# rare.net
KiCad netlist of a schematic drawn in EAGLE
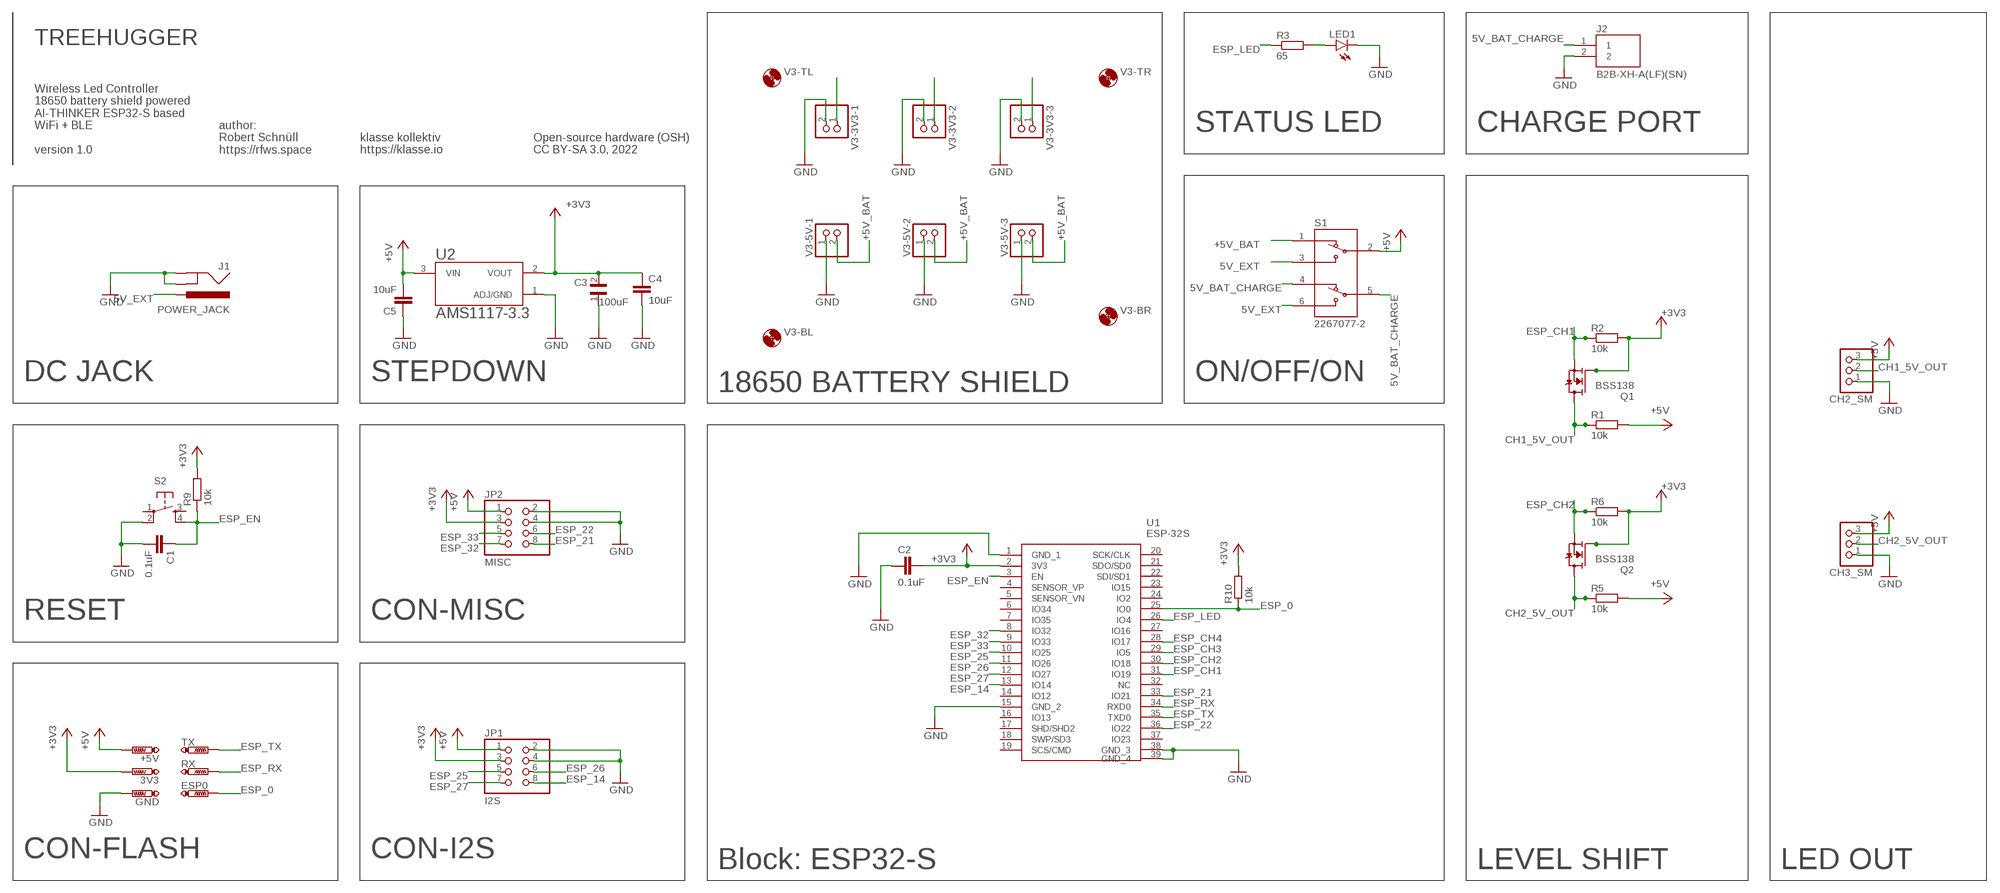
[diagram p0: schematic, sheet 1]

(export (version "E")
  (design (tool "Eeschema 10.0.6"))
  (components
    (comp (ref "+5V")
      (value "PTR1TP15R")
      (footprint "eagle-import:TP15R")
      (libsource (lib "eagle-import") (part "PTR1TP15R"))
    )
    (comp (ref "3V3")
      (value "PTR1TP15R")
      (footprint "eagle-import:TP15R")
      (libsource (lib "eagle-import") (part "PTR1TP15R"))
    )
    (comp (ref "C1")
      (value "0.1uF")
      (footprint "eagle-import:C0805")
      (libsource (lib "eagle-import") (part "C-EUC0805"))
    )
    (comp (ref "C2")
      (value "0.1uF")
      (footprint "eagle-import:C0805")
      (libsource (lib "eagle-import") (part "C-EUC0805"))
    )
    (comp (ref "C3")
      (value "100uF")
      (footprint "eagle-import:CAPPC3528X210N")
      (fields (field (name "MF") "AVX") (field (name "MP") "TAJB107K006RNJ"))
      (libsource (lib "eagle-import") (part "TAJB107K006RNJ"))
    )
    (comp (ref "C4")
      (value "10uF")
      (footprint "eagle-import:C0805")
      (libsource (lib "eagle-import") (part "C-EUC0805"))
    )
    (comp (ref "C5")
      (value "10uF")
      (footprint "eagle-import:C0805")
      (libsource (lib "eagle-import") (part "C-EUC0805"))
    )
    (comp (ref "CH2_SM")
      (value "PINHD-1X3/90")
      (footprint "eagle-import:1X03_90")
      (libsource (lib "eagle-import") (part "PINHD-1X3/90"))
    )
    (comp (ref "CH3_SM")
      (value "PINHD-1X3/90")
      (footprint "eagle-import:1X03_90")
      (libsource (lib "eagle-import") (part "PINHD-1X3/90"))
    )
    (comp (ref "ESP0")
      (value "PTR1TP15R")
      (footprint "eagle-import:TP15R")
      (libsource (lib "eagle-import") (part "PTR1TP15R"))
    )
    (comp (ref "GND")
      (value "PTR1TP15R")
      (footprint "eagle-import:TP15R")
      (libsource (lib "eagle-import") (part "PTR1TP15R"))
    )
    (comp (ref "J1")
      (value "POWER_JACK")
      (footprint "eagle-import:POWER_JACK_PTH")
      (libsource (lib "eagle-import") (part "POWER_JACK"))
    )
    (comp (ref "J2")
      (value "B2B-XH-A(LF)(SN)")
      (footprint "eagle-import:JST_B2B-XH-A(LF)(SN)")
      (fields (field (name "MF") "JST Sales America Inc."))
      (libsource (lib "eagle-import") (part "B2B-XH-A(LF)(SN)"))
    )
    (comp (ref "JP1")
      (value "I2S")
      (footprint "eagle-import:2X04")
      (libsource (lib "eagle-import") (part "PINHD-2X4"))
    )
    (comp (ref "JP2")
      (value "MISC")
      (footprint "eagle-import:2X04")
      (libsource (lib "eagle-import") (part "PINHD-2X4"))
    )
    (comp (ref "LED1")
      (value "LEDCHIP-LED0805")
      (footprint "eagle-import:CHIP-LED0805")
      (libsource (lib "eagle-import") (part "LEDCHIP-LED0805"))
    )
    (comp (ref "Q1")
      (value "BSS138")
      (footprint "eagle-import:SOT23")
      (fields (field (name "MF") "Fairchild"))
      (libsource (lib "eagle-import") (part "BSS138"))
    )
    (comp (ref "Q2")
      (value "BSS138")
      (footprint "eagle-import:SOT23")
      (fields (field (name "MF") "Fairchild"))
      (libsource (lib "eagle-import") (part "BSS138"))
    )
    (comp (ref "R1")
      (value "10k")
      (footprint "eagle-import:R0805")
      (libsource (lib "eagle-import") (part "resistor_348_R-EU_R0805"))
    )
    (comp (ref "R2")
      (value "10k")
      (footprint "eagle-import:R0805")
      (libsource (lib "eagle-import") (part "resistor_348_R-EU_R0805"))
    )
    (comp (ref "R3")
      (value "65")
      (footprint "eagle-import:R0805")
      (libsource (lib "eagle-import") (part "R-EU_R0805"))
    )
    (comp (ref "R5")
      (value "10k")
      (footprint "eagle-import:R0805")
      (libsource (lib "eagle-import") (part "resistor_348_R-EU_R0805"))
    )
    (comp (ref "R6")
      (value "10k")
      (footprint "eagle-import:R0805")
      (libsource (lib "eagle-import") (part "resistor_348_R-EU_R0805"))
    )
    (comp (ref "R9")
      (value "10k")
      (footprint "eagle-import:R0805")
      (libsource (lib "eagle-import") (part "R-EU_R0805"))
    )
    (comp (ref "R10")
      (value "10k")
      (footprint "eagle-import:R0805")
      (libsource (lib "eagle-import") (part "R-EU_R0805"))
    )
    (comp (ref "RX")
      (value "PTR1TP15R")
      (footprint "eagle-import:TP15R")
      (libsource (lib "eagle-import") (part "PTR1TP15R"))
    )
    (comp (ref "S1")
      (value "2267077-2")
      (footprint "eagle-import:TE_2267077-2")
      (fields (field (name "MF") "TE Connectivity"))
      (libsource (lib "eagle-import") (part "2267077-2"))
    )
    (comp (ref "S2")
      (value "TAC_SWITCHSMD")
      (footprint "eagle-import:TACTILE_SWITCH_SMD")
      (libsource (lib "eagle-import") (part "TAC_SWITCHSMD"))
    )
    (comp (ref "TX")
      (value "PTR1TP15R")
      (footprint "eagle-import:TP15R")
      (libsource (lib "eagle-import") (part "PTR1TP15R"))
    )
    (comp (ref "U1")
      (value "ESP-32S")
      (footprint "eagle-import:ESP-32S")
      (fields (field (name "MANUFACTURER_PART_NUMBER") "ESP-32s"))
      (libsource (lib "eagle-import") (part "ESP-32S"))
    )
    (comp (ref "U2")
      (value "AMS1117-3.3")
      (footprint "eagle-import:SOT229P700X180-4N")
      (fields (field (name "MF") "Advanced Monolithic Systems"))
      (libsource (lib "eagle-import") (part "AMS1117-3.3"))
    )
    (comp (ref "V3-3V3-1")
      (value "PINHD-1X2")
      (footprint "eagle-import:1X02")
      (libsource (lib "eagle-import") (part "PINHD-1X2"))
    )
    (comp (ref "V3-3V3-2")
      (value "PINHD-1X2")
      (footprint "eagle-import:1X02")
      (libsource (lib "eagle-import") (part "PINHD-1X2"))
    )
    (comp (ref "V3-3V3-3")
      (value "PINHD-1X2")
      (footprint "eagle-import:1X02")
      (libsource (lib "eagle-import") (part "PINHD-1X2"))
    )
    (comp (ref "V3-5V-1")
      (value "PINHD-1X2")
      (footprint "eagle-import:1X02")
      (libsource (lib "eagle-import") (part "PINHD-1X2"))
    )
    (comp (ref "V3-5V-2")
      (value "PINHD-1X2")
      (footprint "eagle-import:1X02")
      (libsource (lib "eagle-import") (part "PINHD-1X2"))
    )
    (comp (ref "V3-5V-3")
      (value "PINHD-1X2")
      (footprint "eagle-import:1X02")
      (libsource (lib "eagle-import") (part "PINHD-1X2"))
    )
    (comp (ref "V3-BL")
      (value "MOUNT-HOLE3.2")
      (footprint "eagle-import:3,2")
      (libsource (lib "eagle-import") (part "MOUNT-HOLE3.2"))
    )
    (comp (ref "V3-BR")
      (value "MOUNT-HOLE3.2")
      (footprint "eagle-import:3,2")
      (libsource (lib "eagle-import") (part "MOUNT-HOLE3.2"))
    )
    (comp (ref "V3-TL")
      (value "MOUNT-HOLE3.2")
      (footprint "eagle-import:3,2")
      (libsource (lib "eagle-import") (part "MOUNT-HOLE3.2"))
    )
    (comp (ref "V3-TR")
      (value "MOUNT-HOLE3.2")
      (footprint "eagle-import:3,2")
      (libsource (lib "eagle-import") (part "MOUNT-HOLE3.2"))
    )
  )
  (nets
    (net (code "1") (name "+3V3") (class "Default")
      (node (ref "3V3") (pin "TP") (pinfunction "TP_TP") (pintype "input"))
      (node (ref "C2") (pin "2") (pinfunction "2_2") (pintype "passive"))
      (node (ref "C3") (pin "2") (pinfunction "2_2") (pintype "passive"))
      (node (ref "C4") (pin "1") (pinfunction "1_1") (pintype "passive"))
      (node (ref "JP1") (pin "3") (pinfunction "3_3") (pintype "passive"))
      (node (ref "JP2") (pin "3") (pinfunction "3_3") (pintype "passive"))
      (node (ref "Q1") (pin "1") (pinfunction "G_1") (pintype "passive"))
      (node (ref "Q2") (pin "1") (pinfunction "G_1") (pintype "passive"))
      (node (ref "R10") (pin "2") (pinfunction "2_2") (pintype "passive"))
      (node (ref "R2") (pin "2") (pinfunction "2_2") (pintype "passive"))
      (node (ref "R6") (pin "2") (pinfunction "2_2") (pintype "passive"))
      (node (ref "R9") (pin "2") (pinfunction "2_2") (pintype "passive"))
      (node (ref "U1") (pin "2") (pinfunction "3V3_2") (pintype "bidirectional"))
      (node (ref "U2") (pin "2") (pinfunction "VOUT_2") (pintype "output"))
    )
    (net (code "2") (name "+5V") (class "Default")
      (node (ref "+5V") (pin "TP") (pinfunction "TP_TP") (pintype "input"))
      (node (ref "C5") (pin "2") (pinfunction "2_2") (pintype "passive"))
      (node (ref "CH2_SM") (pin "3") (pinfunction "3_3") (pintype "passive"))
      (node (ref "CH3_SM") (pin "3") (pinfunction "3_3") (pintype "passive"))
      (node (ref "JP1") (pin "1") (pinfunction "1_1") (pintype "passive"))
      (node (ref "JP2") (pin "1") (pinfunction "1_1") (pintype "passive"))
      (node (ref "R1") (pin "2") (pinfunction "2_2") (pintype "passive"))
      (node (ref "R5") (pin "2") (pinfunction "2_2") (pintype "passive"))
      (node (ref "S1") (pin "2") (pinfunction "2_2") (pintype "passive"))
      (node (ref "U2") (pin "3") (pinfunction "VIN_3") (pintype "input"))
    )
    (net (code "3") (name "/+5V_BAT") (class "Default")
      (node (ref "S1") (pin "1") (pinfunction "1_1") (pintype "passive"))
      (node (ref "V3-5V-1") (pin "2") (pinfunction "2_2") (pintype "passive"))
      (node (ref "V3-5V-2") (pin "2") (pinfunction "2_2") (pintype "passive"))
      (node (ref "V3-5V-3") (pin "2") (pinfunction "2_2") (pintype "passive"))
    )
    (net (code "4") (name "/5V_BAT_CHARGE") (class "Default")
      (node (ref "J2") (pin "1") (pinfunction "1_1") (pintype "passive"))
      (node (ref "S1") (pin "4") (pinfunction "4_4") (pintype "passive"))
      (node (ref "S1") (pin "5") (pinfunction "5_5") (pintype "passive"))
    )
    (net (code "5") (name "/5V_EXT") (class "Default")
      (node (ref "J1") (pin "PWR") (pinfunction "PWR_PWR") (pintype "bidirectional"))
      (node (ref "S1") (pin "3") (pinfunction "3_3") (pintype "passive"))
      (node (ref "S1") (pin "6") (pinfunction "6_6") (pintype "passive"))
    )
    (net (code "6") (name "/CH1_5V_OUT") (class "Default")
      (node (ref "CH2_SM") (pin "2") (pinfunction "2_2") (pintype "passive"))
      (node (ref "Q1") (pin "3") (pinfunction "D_3") (pintype "passive"))
      (node (ref "R1") (pin "1") (pinfunction "1_1") (pintype "passive"))
    )
    (net (code "7") (name "/CH2_5V_OUT") (class "Default")
      (node (ref "CH3_SM") (pin "2") (pinfunction "2_2") (pintype "passive"))
      (node (ref "Q2") (pin "3") (pinfunction "D_3") (pintype "passive"))
      (node (ref "R5") (pin "1") (pinfunction "1_1") (pintype "passive"))
    )
    (net (code "8") (name "/ESP_0") (class "Default")
      (node (ref "ESP0") (pin "TP") (pinfunction "TP_TP") (pintype "input"))
      (node (ref "R10") (pin "1") (pinfunction "1_1") (pintype "passive"))
      (node (ref "U1") (pin "25") (pinfunction "IO0_25") (pintype "bidirectional"))
    )
    (net (code "9") (name "/ESP_14") (class "Default")
      (node (ref "JP1") (pin "8") (pinfunction "8_8") (pintype "passive"))
      (node (ref "U1") (pin "13") (pinfunction "IO14_13") (pintype "bidirectional"))
    )
    (net (code "10") (name "/ESP_21") (class "Default")
      (node (ref "JP2") (pin "8") (pinfunction "8_8") (pintype "passive"))
      (node (ref "U1") (pin "33") (pinfunction "IO21_33") (pintype "bidirectional"))
    )
    (net (code "11") (name "/ESP_22") (class "Default")
      (node (ref "JP2") (pin "6") (pinfunction "6_6") (pintype "passive"))
      (node (ref "U1") (pin "36") (pinfunction "IO22_36") (pintype "bidirectional"))
    )
    (net (code "12") (name "/ESP_25") (class "Default")
      (node (ref "JP1") (pin "5") (pinfunction "5_5") (pintype "passive"))
      (node (ref "U1") (pin "10") (pinfunction "IO25_10") (pintype "bidirectional"))
    )
    (net (code "13") (name "/ESP_26") (class "Default")
      (node (ref "JP1") (pin "6") (pinfunction "6_6") (pintype "passive"))
      (node (ref "U1") (pin "11") (pinfunction "IO26_11") (pintype "bidirectional"))
    )
    (net (code "14") (name "/ESP_27") (class "Default")
      (node (ref "JP1") (pin "7") (pinfunction "7_7") (pintype "passive"))
      (node (ref "U1") (pin "12") (pinfunction "IO27_12") (pintype "bidirectional"))
    )
    (net (code "15") (name "/ESP_32") (class "Default")
      (node (ref "JP2") (pin "7") (pinfunction "7_7") (pintype "passive"))
      (node (ref "U1") (pin "8") (pinfunction "IO32_8") (pintype "bidirectional"))
    )
    (net (code "16") (name "/ESP_33") (class "Default")
      (node (ref "JP2") (pin "5") (pinfunction "5_5") (pintype "passive"))
      (node (ref "U1") (pin "9") (pinfunction "IO33_9") (pintype "bidirectional"))
    )
    (net (code "17") (name "/ESP_CH1") (class "Default")
      (node (ref "Q1") (pin "2") (pinfunction "S_2") (pintype "passive"))
      (node (ref "R2") (pin "1") (pinfunction "1_1") (pintype "passive"))
      (node (ref "U1") (pin "31") (pinfunction "IO19_31") (pintype "bidirectional"))
    )
    (net (code "18") (name "/ESP_CH2") (class "Default")
      (node (ref "Q2") (pin "2") (pinfunction "S_2") (pintype "passive"))
      (node (ref "R6") (pin "1") (pinfunction "1_1") (pintype "passive"))
      (node (ref "U1") (pin "30") (pinfunction "IO18_30") (pintype "bidirectional"))
    )
    (net (code "19") (name "/ESP_CH3") (class "Default")
      (node (ref "U1") (pin "29") (pinfunction "IO5_29") (pintype "bidirectional"))
    )
    (net (code "20") (name "/ESP_CH4") (class "Default")
      (node (ref "U1") (pin "28") (pinfunction "IO17_28") (pintype "bidirectional"))
    )
    (net (code "21") (name "/ESP_EN") (class "Default")
      (node (ref "C1") (pin "1") (pinfunction "1_1") (pintype "passive"))
      (node (ref "R9") (pin "1") (pinfunction "1_1") (pintype "passive"))
      (node (ref "S2") (pin "4") (pinfunction "4_4") (pintype "passive"))
      (node (ref "U1") (pin "3") (pinfunction "EN_3") (pintype "bidirectional"))
    )
    (net (code "22") (name "/ESP_LED") (class "Default")
      (node (ref "R3") (pin "1") (pinfunction "1_1") (pintype "passive"))
      (node (ref "U1") (pin "26") (pinfunction "IO4_26") (pintype "bidirectional"))
    )
    (net (code "23") (name "/ESP_RX") (class "Default")
      (node (ref "RX") (pin "TP") (pinfunction "TP_TP") (pintype "input"))
      (node (ref "U1") (pin "34") (pinfunction "RXD0_34") (pintype "bidirectional"))
    )
    (net (code "24") (name "/ESP_TX") (class "Default")
      (node (ref "TX") (pin "TP") (pinfunction "TP_TP") (pintype "input"))
      (node (ref "U1") (pin "35") (pinfunction "TXD0_35") (pintype "bidirectional"))
    )
    (net (code "25") (name "GND") (class "Default")
      (node (ref "C1") (pin "2") (pinfunction "2_2") (pintype "passive"))
      (node (ref "C2") (pin "1") (pinfunction "1_1") (pintype "passive"))
      (node (ref "C3") (pin "1") (pinfunction "1_1") (pintype "passive"))
      (node (ref "C4") (pin "2") (pinfunction "2_2") (pintype "passive"))
      (node (ref "C5") (pin "1") (pinfunction "1_1") (pintype "passive"))
      (node (ref "CH2_SM") (pin "1") (pinfunction "1_1") (pintype "passive"))
      (node (ref "CH3_SM") (pin "1") (pinfunction "1_1") (pintype "passive"))
      (node (ref "GND") (pin "TP") (pinfunction "TP_TP") (pintype "input"))
      (node (ref "J1") (pin "GND") (pinfunction "GND_GND") (pintype "bidirectional"))
      (node (ref "J1") (pin "GNDBREAK") (pinfunction "GNDBREAK_GNDBREAK") (pintype "bidirectional"))
      (node (ref "J2") (pin "2") (pinfunction "2_2") (pintype "passive"))
      (node (ref "JP1") (pin "2") (pinfunction "2_2") (pintype "passive"))
      (node (ref "JP1") (pin "4") (pinfunction "4_4") (pintype "passive"))
      (node (ref "JP2") (pin "2") (pinfunction "2_2") (pintype "passive"))
      (node (ref "JP2") (pin "4") (pinfunction "4_4") (pintype "passive"))
      (node (ref "LED1") (pin "C") (pinfunction "C_C") (pintype "passive"))
      (node (ref "S2") (pin "2") (pinfunction "2_2") (pintype "passive"))
      (node (ref "U1") (pin "1") (pinfunction "GND_1_1") (pintype "bidirectional"))
      (node (ref "U1") (pin "15") (pinfunction "GND_2_15") (pintype "bidirectional"))
      (node (ref "U1") (pin "38") (pinfunction "GND_3_38") (pintype "bidirectional"))
      (node (ref "U1") (pin "39") (pinfunction "GND_4_39") (pintype "bidirectional"))
      (node (ref "U2") (pin "1") (pinfunction "ADJ/GND_1") (pintype "power_in"))
      (node (ref "V3-3V3-1") (pin "2") (pinfunction "2_2") (pintype "passive"))
      (node (ref "V3-3V3-2") (pin "2") (pinfunction "2_2") (pintype "passive"))
      (node (ref "V3-3V3-3") (pin "2") (pinfunction "2_2") (pintype "passive"))
      (node (ref "V3-5V-1") (pin "1") (pinfunction "1_1") (pintype "passive"))
      (node (ref "V3-5V-2") (pin "1") (pinfunction "1_1") (pintype "passive"))
      (node (ref "V3-5V-3") (pin "1") (pinfunction "1_1") (pintype "passive"))
    )
    (net (code "26") (name "Net-(LED1-PadA)") (class "Default")
      (node (ref "LED1") (pin "A") (pinfunction "A_A") (pintype "passive"))
      (node (ref "R3") (pin "2") (pinfunction "2_2") (pintype "passive"))
    )
    (net (code "27") (name "unconnected-(S2-Pad1)") (class "Default")
      (node (ref "S2") (pin "1") (pinfunction "1_1") (pintype "passive"))
    )
    (net (code "28") (name "unconnected-(S2-Pad3)") (class "Default")
      (node (ref "S2") (pin "3") (pinfunction "3_3") (pintype "passive"))
    )
    (net (code "29") (name "unconnected-(U1-IO2-Pad24)") (class "Default")
      (node (ref "U1") (pin "24") (pinfunction "IO2_24") (pintype "bidirectional"))
    )
    (net (code "30") (name "unconnected-(U1-IO12-Pad14)") (class "Default")
      (node (ref "U1") (pin "14") (pinfunction "IO12_14") (pintype "bidirectional"))
    )
    (net (code "31") (name "unconnected-(U1-IO13-Pad16)") (class "Default")
      (node (ref "U1") (pin "16") (pinfunction "IO13_16") (pintype "bidirectional"))
    )
    (net (code "32") (name "unconnected-(U1-IO15-Pad23)") (class "Default")
      (node (ref "U1") (pin "23") (pinfunction "IO15_23") (pintype "bidirectional"))
    )
    (net (code "33") (name "unconnected-(U1-IO16-Pad27)") (class "Default")
      (node (ref "U1") (pin "27") (pinfunction "IO16_27") (pintype "bidirectional"))
    )
    (net (code "34") (name "unconnected-(U1-IO23-Pad37)") (class "Default")
      (node (ref "U1") (pin "37") (pinfunction "IO23_37") (pintype "bidirectional"))
    )
    (net (code "35") (name "unconnected-(U1-IO34-Pad6)") (class "Default")
      (node (ref "U1") (pin "6") (pinfunction "IO34_6") (pintype "bidirectional"))
    )
    (net (code "36") (name "unconnected-(U1-IO35-Pad7)") (class "Default")
      (node (ref "U1") (pin "7") (pinfunction "IO35_7") (pintype "bidirectional"))
    )
    (net (code "37") (name "unconnected-(U1-NC-Pad32)") (class "Default")
      (node (ref "U1") (pin "32") (pinfunction "NC_32") (pintype "no_connect"))
    )
    (net (code "38") (name "unconnected-(U1-SCK{slash}CLK-Pad20)") (class "Default")
      (node (ref "U1") (pin "20") (pinfunction "SCK/CLK_20") (pintype "bidirectional"))
    )
    (net (code "39") (name "unconnected-(U1-SCS{slash}CMD-Pad19)") (class "Default")
      (node (ref "U1") (pin "19") (pinfunction "SCS/CMD_19") (pintype "bidirectional"))
    )
    (net (code "40") (name "unconnected-(U1-SDI{slash}SD1-Pad22)") (class "Default")
      (node (ref "U1") (pin "22") (pinfunction "SDI/SD1_22") (pintype "bidirectional"))
    )
    (net (code "41") (name "unconnected-(U1-SDO{slash}SD0-Pad21)") (class "Default")
      (node (ref "U1") (pin "21") (pinfunction "SDO/SD0_21") (pintype "bidirectional"))
    )
    (net (code "42") (name "unconnected-(U1-SENSOR_VN-Pad5)") (class "Default")
      (node (ref "U1") (pin "5") (pinfunction "SENSOR_VN_5") (pintype "bidirectional"))
    )
    (net (code "43") (name "unconnected-(U1-SENSOR_VP-Pad4)") (class "Default")
      (node (ref "U1") (pin "4") (pinfunction "SENSOR_VP_4") (pintype "bidirectional"))
    )
    (net (code "44") (name "unconnected-(U1-SHD{slash}SHD2-Pad17)") (class "Default")
      (node (ref "U1") (pin "17") (pinfunction "SHD/SHD2_17") (pintype "bidirectional"))
    )
    (net (code "45") (name "unconnected-(U1-SWP{slash}SD3-Pad18)") (class "Default")
      (node (ref "U1") (pin "18") (pinfunction "SWP/SD3_18") (pintype "bidirectional"))
    )
    (net (code "46") (name "unconnected-(V3-3V3-1-Pad1)") (class "Default")
      (node (ref "V3-3V3-1") (pin "1") (pinfunction "1_1") (pintype "passive"))
    )
    (net (code "47") (name "unconnected-(V3-3V3-2-Pad1)") (class "Default")
      (node (ref "V3-3V3-2") (pin "1") (pinfunction "1_1") (pintype "passive"))
    )
    (net (code "48") (name "unconnected-(V3-3V3-3-Pad1)") (class "Default")
      (node (ref "V3-3V3-3") (pin "1") (pinfunction "1_1") (pintype "passive"))
    )
  )
)
